# power.net
KiCad netlist of a schematic drawn in EAGLE
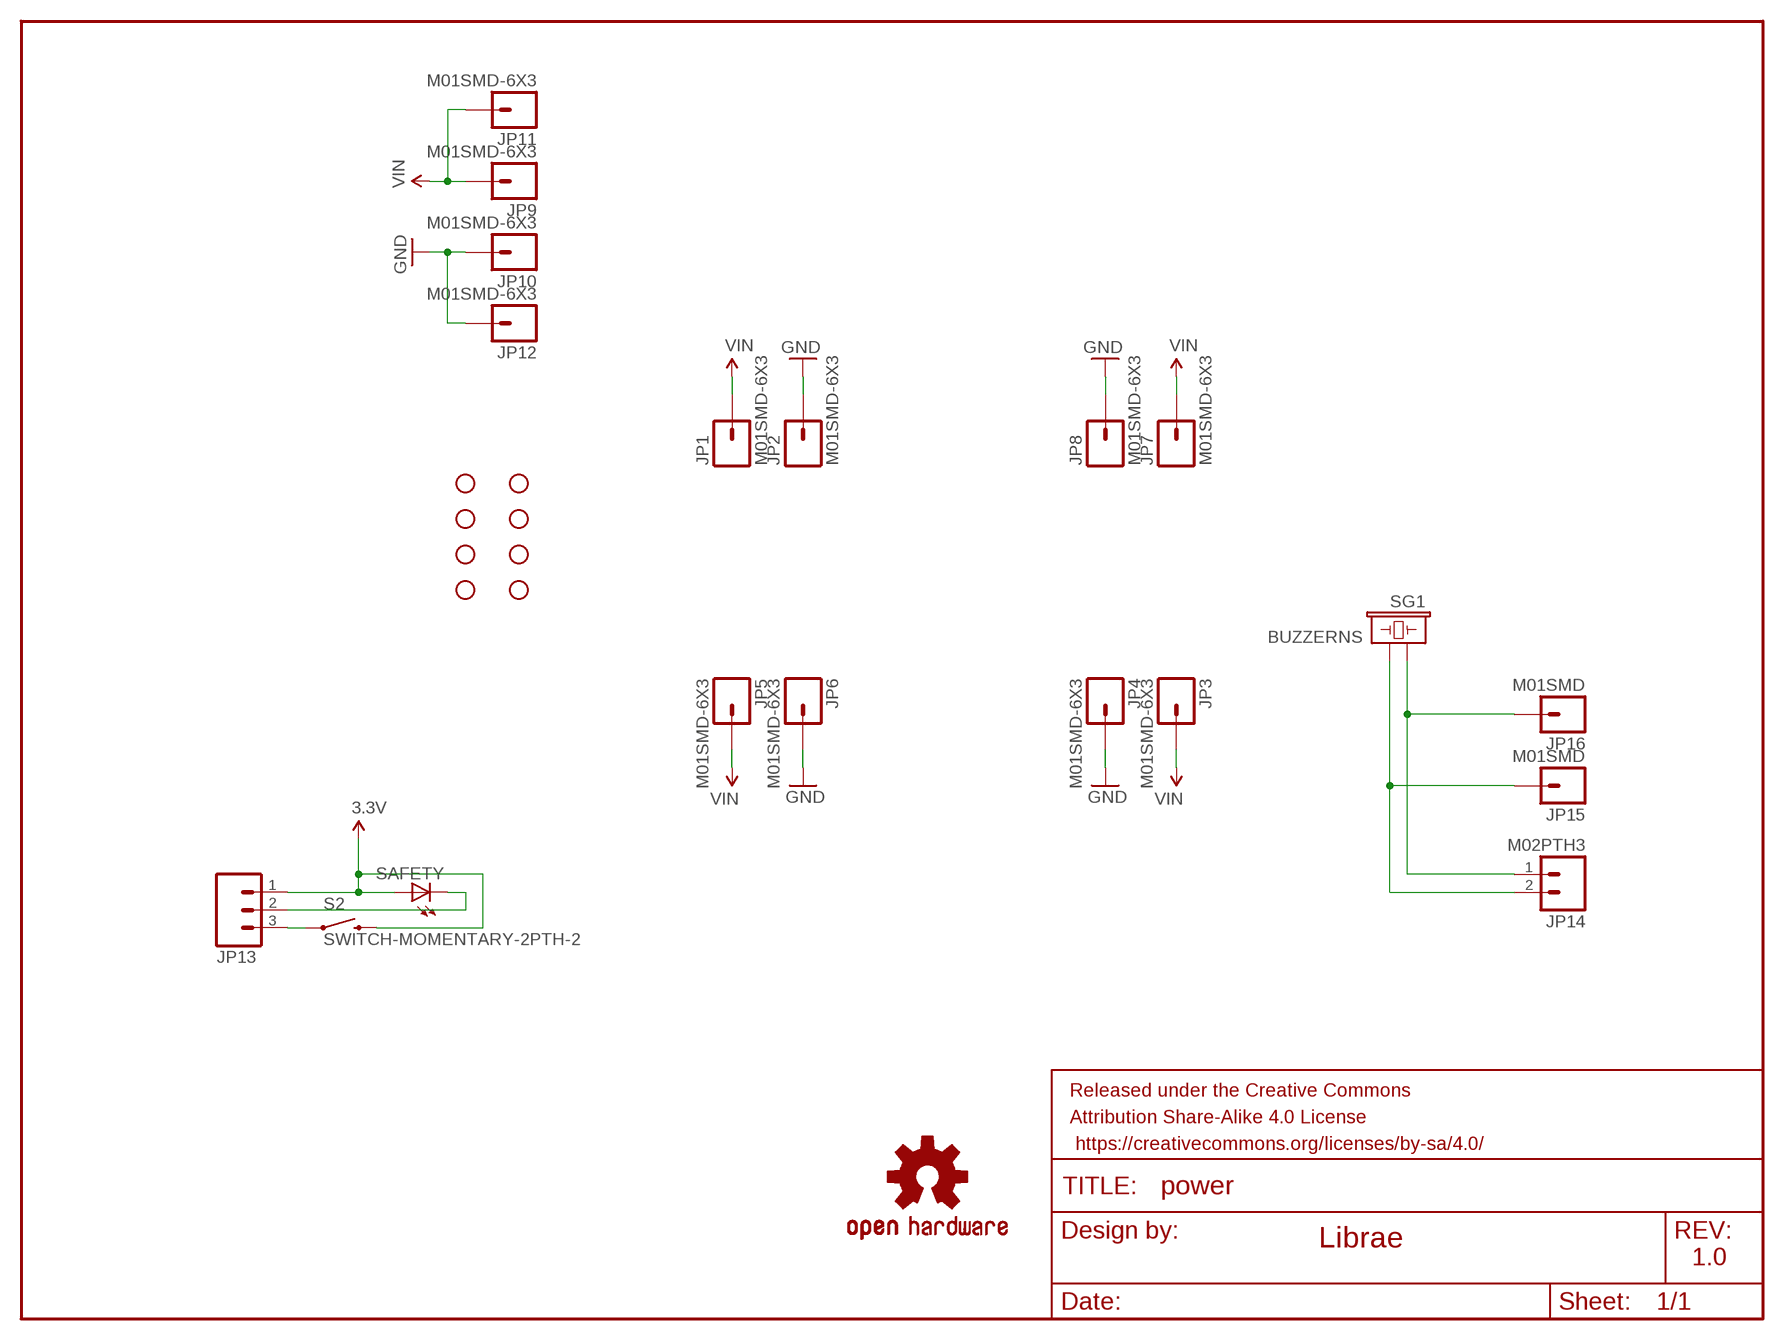
[diagram p0: schematic, sheet 1]

(export (version "E")
  (design (tool "Eeschema 10.0.6"))
  (components
    (comp (ref "FRAME1")
      (value "FRAME-LETTER")
      (footprint "eagle-import:CREATIVE_COMMONS")
      (libsource (lib "eagle-import") (part "FRAME-LETTER"))
    )
    (comp (ref "JP1")
      (value "M01SMD-6X3")
      (footprint "eagle-import:PAD-BULLET")
      (libsource (lib "eagle-import") (part "M01SMD-6X3"))
    )
    (comp (ref "JP2")
      (value "M01SMD-6X3")
      (footprint "eagle-import:PAD-BULLET")
      (libsource (lib "eagle-import") (part "M01SMD-6X3"))
    )
    (comp (ref "JP3")
      (value "M01SMD-6X3")
      (footprint "eagle-import:PAD-BULLET")
      (libsource (lib "eagle-import") (part "M01SMD-6X3"))
    )
    (comp (ref "JP4")
      (value "M01SMD-6X3")
      (footprint "eagle-import:PAD-BULLET")
      (libsource (lib "eagle-import") (part "M01SMD-6X3"))
    )
    (comp (ref "JP5")
      (value "M01SMD-6X3")
      (footprint "eagle-import:PAD-BULLET")
      (libsource (lib "eagle-import") (part "M01SMD-6X3"))
    )
    (comp (ref "JP6")
      (value "M01SMD-6X3")
      (footprint "eagle-import:PAD-BULLET")
      (libsource (lib "eagle-import") (part "M01SMD-6X3"))
    )
    (comp (ref "JP7")
      (value "M01SMD-6X3")
      (footprint "eagle-import:PAD-BULLET")
      (libsource (lib "eagle-import") (part "M01SMD-6X3"))
    )
    (comp (ref "JP8")
      (value "M01SMD-6X3")
      (footprint "eagle-import:PAD-BULLET")
      (libsource (lib "eagle-import") (part "M01SMD-6X3"))
    )
    (comp (ref "JP9")
      (value "M01SMD-6X3")
      (footprint "eagle-import:PAD-BULLET")
      (libsource (lib "eagle-import") (part "M01SMD-6X3"))
    )
    (comp (ref "JP10")
      (value "M01SMD-6X3")
      (footprint "eagle-import:PAD-BULLET")
      (libsource (lib "eagle-import") (part "M01SMD-6X3"))
    )
    (comp (ref "JP11")
      (value "M01SMD-6X3")
      (footprint "eagle-import:PAD-BULLET")
      (libsource (lib "eagle-import") (part "M01SMD-6X3"))
    )
    (comp (ref "JP12")
      (value "M01SMD-6X3")
      (footprint "eagle-import:PAD-BULLET")
      (libsource (lib "eagle-import") (part "M01SMD-6X3"))
    )
    (comp (ref "JP13")
      (value "M03LONGPADS")
      (footprint "eagle-import:1X03_LONGPADS")
      (libsource (lib "eagle-import") (part "M03LONGPADS"))
    )
    (comp (ref "JP14")
      (value "M02PTH3")
      (footprint "eagle-import:1X02_LONGPADS")
      (libsource (lib "eagle-import") (part "M02PTH3"))
    )
    (comp (ref "JP15")
      (value "M01SMD")
      (footprint "eagle-import:LUXEON-PAD")
      (libsource (lib "eagle-import") (part "M01SMD"))
    )
    (comp (ref "JP16")
      (value "M01SMD")
      (footprint "eagle-import:LUXEON-PAD")
      (libsource (lib "eagle-import") (part "M01SMD"))
    )
    (comp (ref "LOGO1")
      (value "OSHW-LOGOL")
      (footprint "eagle-import:OSHW-LOGO-L")
      (libsource (lib "eagle-import") (part "OSHW-LOGOL"))
    )
    (comp (ref "S2")
      (value "SWITCH-MOMENTARY-2PTH-2")
      (footprint "eagle-import:TACTILE-PTH-2")
      (libsource (lib "eagle-import") (part "SWITCH-MOMENTARY-2PTH-2"))
    )
    (comp (ref "SAFETY")
      (value "LED5MM")
      (footprint "eagle-import:LED5MM")
      (libsource (lib "eagle-import") (part "LED5MM"))
    )
    (comp (ref "SG1")
      (value "BUZZERNS")
      (footprint "eagle-import:BUZZER-12MM-NS")
      (libsource (lib "eagle-import") (part "BUZZERNS"))
    )
    (comp (ref "STANDOFF1")
      (value "STAND-OFF")
      (footprint "eagle-import:STAND-OFF")
      (libsource (lib "eagle-import") (part "STAND-OFF"))
    )
    (comp (ref "STANDOFF2")
      (value "STAND-OFF")
      (footprint "eagle-import:STAND-OFF")
      (libsource (lib "eagle-import") (part "STAND-OFF"))
    )
    (comp (ref "STANDOFF3")
      (value "STAND-OFF")
      (footprint "eagle-import:STAND-OFF")
      (libsource (lib "eagle-import") (part "STAND-OFF"))
    )
    (comp (ref "STANDOFF4")
      (value "STAND-OFF")
      (footprint "eagle-import:STAND-OFF")
      (libsource (lib "eagle-import") (part "STAND-OFF"))
    )
    (comp (ref "STANDOFF5")
      (value "STAND-OFF")
      (footprint "eagle-import:STAND-OFF")
      (libsource (lib "eagle-import") (part "STAND-OFF"))
    )
    (comp (ref "STANDOFF6")
      (value "STAND-OFF")
      (footprint "eagle-import:STAND-OFF")
      (libsource (lib "eagle-import") (part "STAND-OFF"))
    )
    (comp (ref "STANDOFF7")
      (value "STAND-OFF")
      (footprint "eagle-import:STAND-OFF")
      (libsource (lib "eagle-import") (part "STAND-OFF"))
    )
    (comp (ref "STANDOFF8")
      (value "STAND-OFF")
      (footprint "eagle-import:STAND-OFF")
      (libsource (lib "eagle-import") (part "STAND-OFF"))
    )
  )
  (nets
    (net (code "1") (name "3.3V") (class "Default")
      (node (ref "JP13") (pin "1") (pinfunction "1_1") (pintype "passive"))
      (node (ref "S2") (pin "4") (pinfunction "2_4") (pintype "passive"))
      (node (ref "SAFETY") (pin "A") (pinfunction "A_A") (pintype "passive"))
    )
    (net (code "2") (name "GND") (class "Default")
      (node (ref "JP10") (pin "P$1") (pinfunction "1_P$1") (pintype "passive"))
      (node (ref "JP12") (pin "P$1") (pinfunction "1_P$1") (pintype "passive"))
      (node (ref "JP2") (pin "P$1") (pinfunction "1_P$1") (pintype "passive"))
      (node (ref "JP4") (pin "P$1") (pinfunction "1_P$1") (pintype "passive"))
      (node (ref "JP6") (pin "P$1") (pinfunction "1_P$1") (pintype "passive"))
      (node (ref "JP8") (pin "P$1") (pinfunction "1_P$1") (pintype "passive"))
    )
    (net (code "3") (name "Net-(JP13-Pad3)") (class "Default")
      (node (ref "JP13") (pin "3") (pinfunction "3_3") (pintype "passive"))
      (node (ref "S2") (pin "1") (pinfunction "1_1") (pintype "passive"))
    )
    (net (code "4") (name "Net-(JP15-1)") (class "Default")
      (node (ref "JP14") (pin "2") (pinfunction "2_2") (pintype "passive"))
      (node (ref "JP15") (pin "P$1") (pinfunction "1_P$1") (pintype "passive"))
      (node (ref "SG1") (pin "-") (pinfunction "2_-") (pintype "passive"))
    )
    (net (code "5") (name "Net-(JP16-1)") (class "Default")
      (node (ref "JP14") (pin "1") (pinfunction "1_1") (pintype "passive"))
      (node (ref "JP16") (pin "P$1") (pinfunction "1_P$1") (pintype "passive"))
      (node (ref "SG1") (pin "+") (pinfunction "1_+") (pintype "passive"))
    )
    (net (code "6") (name "Net-(SAFETY-C)") (class "Default")
      (node (ref "JP13") (pin "2") (pinfunction "2_2") (pintype "passive"))
      (node (ref "SAFETY") (pin "K") (pinfunction "C_K") (pintype "passive"))
    )
    (net (code "7") (name "VIN") (class "Default")
      (node (ref "JP1") (pin "P$1") (pinfunction "1_P$1") (pintype "passive"))
      (node (ref "JP11") (pin "P$1") (pinfunction "1_P$1") (pintype "passive"))
      (node (ref "JP3") (pin "P$1") (pinfunction "1_P$1") (pintype "passive"))
      (node (ref "JP5") (pin "P$1") (pinfunction "1_P$1") (pintype "passive"))
      (node (ref "JP7") (pin "P$1") (pinfunction "1_P$1") (pintype "passive"))
      (node (ref "JP9") (pin "P$1") (pinfunction "1_P$1") (pintype "passive"))
    )
  )
)
